# -0_1-0_8.net
KiCad netlist of a schematic drawn in EAGLE
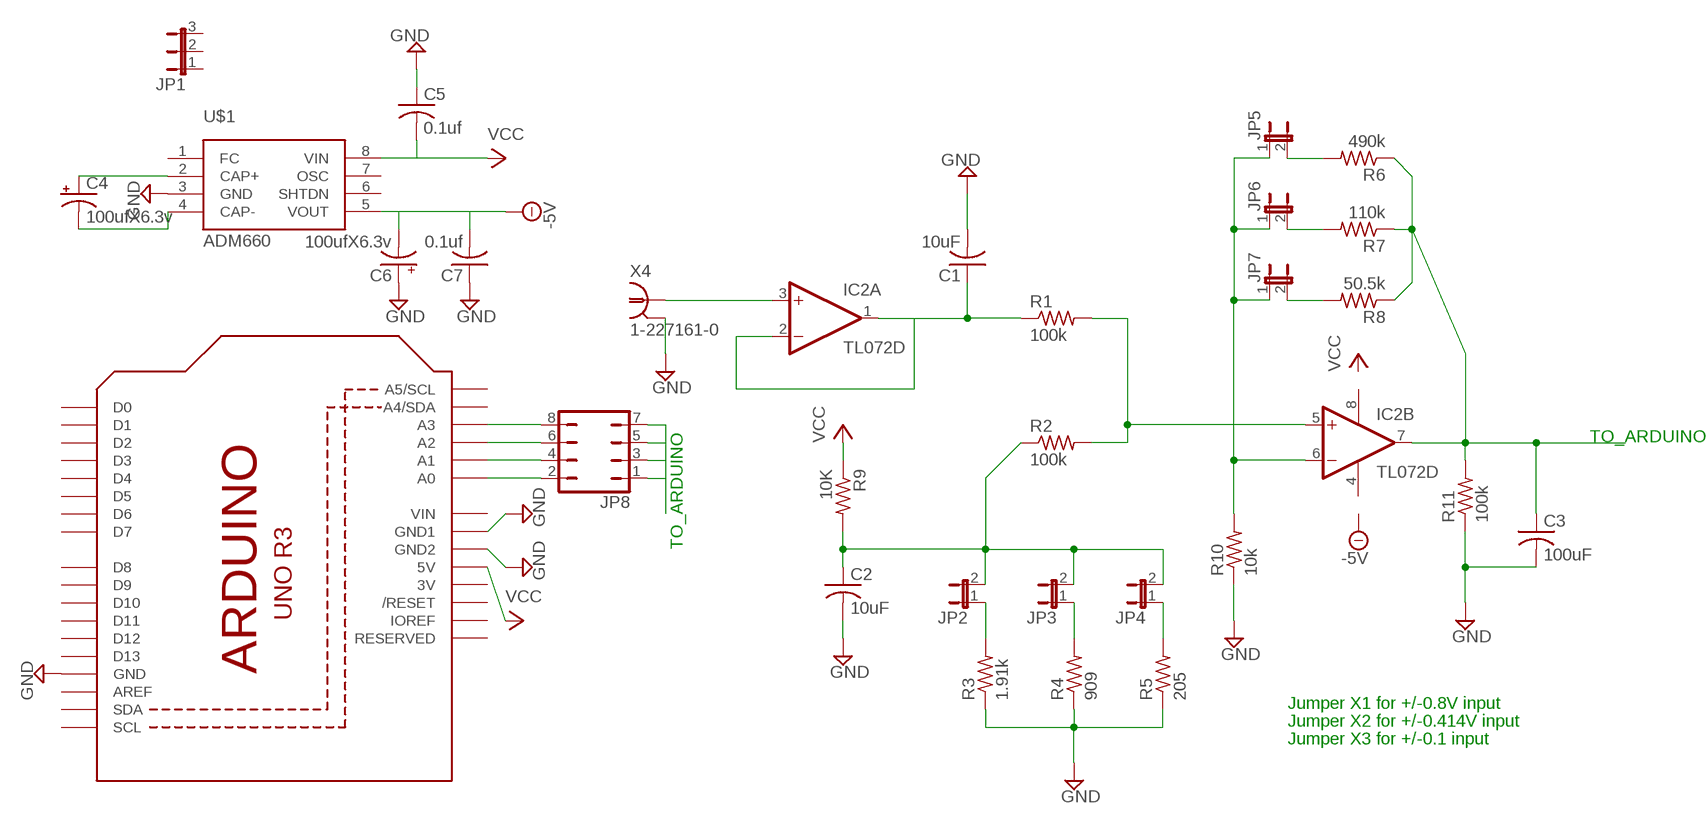
[diagram p0: schematic, sheet 1]

(export (version "E")
  (design (tool "Eeschema 10.0.6"))
  (components
    (comp (ref "C1")
      (value "10uF")
      (footprint "eagle-import:C0603")
      (libsource (lib "eagle-import") (part "resistor_C-USC0603"))
    )
    (comp (ref "C2")
      (value "10uF")
      (footprint "eagle-import:C0603")
      (libsource (lib "eagle-import") (part "resistor_C-USC0603"))
    )
    (comp (ref "C3")
      (value "100uF")
      (footprint "eagle-import:C0603")
      (libsource (lib "eagle-import") (part "resistor_C-USC0603"))
    )
    (comp (ref "C4")
      (value "100ufX6.3v")
      (footprint "eagle-import:153CLV-0605")
      (libsource (lib "eagle-import") (part "CPOL-US153CLV-0605"))
    )
    (comp (ref "C5")
      (value "0.1uf")
      (footprint "eagle-import:C0603")
      (libsource (lib "eagle-import") (part "C-USC0603"))
    )
    (comp (ref "C6")
      (value "100ufX6.3v")
      (footprint "eagle-import:153CLV-0605")
      (libsource (lib "eagle-import") (part "CPOL-US153CLV-0605"))
    )
    (comp (ref "C7")
      (value "0.1uf")
      (footprint "eagle-import:C0603")
      (libsource (lib "eagle-import") (part "C-USC0603"))
    )
    (comp (ref "IC2")
      (value "TL072D")
      (footprint "eagle-import:SO08")
      (libsource (lib "eagle-import") (part "TL072D"))
    )
    (comp (ref "JP1")
      (value "JP2E")
      (footprint "eagle-import:JP2")
      (libsource (lib "eagle-import") (part "JP2E"))
    )
    (comp (ref "JP2")
      (value "JP1E")
      (footprint "eagle-import:JP1")
      (libsource (lib "eagle-import") (part "JP1E"))
    )
    (comp (ref "JP3")
      (value "JP1E")
      (footprint "eagle-import:JP1")
      (libsource (lib "eagle-import") (part "JP1E"))
    )
    (comp (ref "JP4")
      (value "JP1E")
      (footprint "eagle-import:JP1")
      (libsource (lib "eagle-import") (part "JP1E"))
    )
    (comp (ref "JP5")
      (value "JP1E")
      (footprint "eagle-import:JP1")
      (libsource (lib "eagle-import") (part "JP1E"))
    )
    (comp (ref "JP6")
      (value "JP1E")
      (footprint "eagle-import:JP1")
      (libsource (lib "eagle-import") (part "JP1E"))
    )
    (comp (ref "JP7")
      (value "JP1E")
      (footprint "eagle-import:JP1")
      (libsource (lib "eagle-import") (part "JP1E"))
    )
    (comp (ref "JP8")
      (value "JP4Q")
      (footprint "eagle-import:JP4Q")
      (libsource (lib "eagle-import") (part "JP4Q"))
    )
    (comp (ref "R1")
      (value "100k")
      (footprint "eagle-import:R0603")
      (libsource (lib "eagle-import") (part "R-US_R0603"))
    )
    (comp (ref "R2")
      (value "100k")
      (footprint "eagle-import:R0603")
      (libsource (lib "eagle-import") (part "R-US_R0603"))
    )
    (comp (ref "R3")
      (value "1.91k")
      (footprint "eagle-import:R0603")
      (libsource (lib "eagle-import") (part "R-US_R0603"))
    )
    (comp (ref "R4")
      (value "909")
      (footprint "eagle-import:R0603")
      (libsource (lib "eagle-import") (part "R-US_R0603"))
    )
    (comp (ref "R5")
      (value "205")
      (footprint "eagle-import:R0603")
      (libsource (lib "eagle-import") (part "R-US_R0603"))
    )
    (comp (ref "R6")
      (value "490k")
      (footprint "eagle-import:R0603")
      (libsource (lib "eagle-import") (part "R-US_R0603"))
    )
    (comp (ref "R7")
      (value "110k")
      (footprint "eagle-import:R0603")
      (libsource (lib "eagle-import") (part "R-US_R0603"))
    )
    (comp (ref "R8")
      (value "50.5k")
      (footprint "eagle-import:R0603")
      (libsource (lib "eagle-import") (part "R-US_R0603"))
    )
    (comp (ref "R9")
      (value "10K")
      (footprint "eagle-import:R0603")
      (libsource (lib "eagle-import") (part "R-US_R0603"))
    )
    (comp (ref "R10")
      (value "10k")
      (footprint "eagle-import:R0603")
      (libsource (lib "eagle-import") (part "R-US_R0603"))
    )
    (comp (ref "R11")
      (value "100k")
      (footprint "eagle-import:R0603")
      (libsource (lib "eagle-import") (part "R-US_R0603"))
    )
    (comp (ref "U$1")
      (value "ADM660")
      (footprint "eagle-import:SO8")
      (libsource (lib "eagle-import") (part "TC1121COA"))
    )
    (comp (ref "U1")
      (value "ARDUINOR3-DIMENSION")
      (footprint "eagle-import:ARDUINOR3")
      (libsource (lib "eagle-import") (part "ARDUINOR3-DIMENSION"))
    )
    (comp (ref "X4")
      (value "1-227161-0")
      (footprint "eagle-import:AMP_227161")
      (fields (field (name "MF") "TYCO ELECTRONICS") (field (name "MPN") "1-227161"))
      (libsource (lib "eagle-import") (part "?2271611--0"))
    )
  )
  (nets
    (net (code "1") (name "-5V") (class "Default")
      (node (ref "C6") (pin "-") (pinfunction "-_-") (pintype "passive"))
      (node (ref "C7") (pin "2") (pinfunction "2_2") (pintype "passive"))
      (node (ref "U$1") (pin "5") (pinfunction "VOUT_5") (pintype "bidirectional"))
    )
    (net (code "2") (name "/3V") (class "Default")
      (node (ref "U1") (pin "3V") (pinfunction "3V_3V") (pintype "power_in"))
    )
    (net (code "3") (name "/TO_ARDUINO") (class "Default")
      (node (ref "C3") (pin "1") (pinfunction "1_1") (pintype "passive"))
      (node (ref "IC2") (pin "7") (pinfunction "OUT_7") (pintype "output"))
      (node (ref "JP8") (pin "1") (pinfunction "1_1") (pintype "passive"))
      (node (ref "JP8") (pin "3") (pinfunction "3_3") (pintype "passive"))
      (node (ref "JP8") (pin "5") (pinfunction "5_5") (pintype "passive"))
      (node (ref "JP8") (pin "7") (pinfunction "7_7") (pintype "passive"))
      (node (ref "R11") (pin "2") (pinfunction "2_2") (pintype "passive"))
      (node (ref "R6") (pin "1") (pinfunction "1_1") (pintype "passive"))
      (node (ref "R7") (pin "1") (pinfunction "1_1") (pintype "passive"))
      (node (ref "R8") (pin "1") (pinfunction "1_1") (pintype "passive"))
    )
    (net (code "4") (name "/V+") (class "Default")
      (node (ref "IC2") (pin "8") (pinfunction "V+_8") (pintype "power_in"))
    )
    (net (code "5") (name "/V-") (class "Default")
      (node (ref "IC2") (pin "4") (pinfunction "V-_4") (pintype "power_in"))
    )
    (net (code "6") (name "/VIN") (class "Default")
      (node (ref "U1") (pin "VIN") (pinfunction "VIN_VIN") (pintype "power_in"))
    )
    (net (code "7") (name "GND") (class "Default")
      (node (ref "C1") (pin "2") (pinfunction "2_2") (pintype "passive"))
      (node (ref "C2") (pin "2") (pinfunction "2_2") (pintype "passive"))
      (node (ref "C3") (pin "2") (pinfunction "2_2") (pintype "passive"))
      (node (ref "C5") (pin "1") (pinfunction "1_1") (pintype "passive"))
      (node (ref "C6") (pin "+") (pinfunction "+_+") (pintype "passive"))
      (node (ref "C7") (pin "1") (pinfunction "1_1") (pintype "passive"))
      (node (ref "R10") (pin "1") (pinfunction "1_1") (pintype "passive"))
      (node (ref "R11") (pin "1") (pinfunction "1_1") (pintype "passive"))
      (node (ref "R3") (pin "1") (pinfunction "1_1") (pintype "passive"))
      (node (ref "R4") (pin "1") (pinfunction "1_1") (pintype "passive"))
      (node (ref "R5") (pin "1") (pinfunction "1_1") (pintype "passive"))
      (node (ref "U$1") (pin "3") (pinfunction "GND_3") (pintype "bidirectional"))
      (node (ref "U1") (pin "GND") (pinfunction "GND_GND") (pintype "power_in"))
      (node (ref "U1") (pin "GND1") (pinfunction "GND1_GND1") (pintype "power_in"))
      (node (ref "U1") (pin "GND2") (pinfunction "GND2_GND2") (pintype "power_in"))
      (node (ref "X4") (pin "2") (pinfunction "GND_2") (pintype "power_in"))
    )
    (net (code "8") (name "Net-(C2-Pad1)") (class "Default")
      (node (ref "C2") (pin "1") (pinfunction "1_1") (pintype "passive"))
      (node (ref "JP2") (pin "2") (pinfunction "2_2") (pintype "passive"))
      (node (ref "JP3") (pin "2") (pinfunction "2_2") (pintype "passive"))
      (node (ref "JP4") (pin "2") (pinfunction "2_2") (pintype "passive"))
      (node (ref "R2") (pin "1") (pinfunction "1_1") (pintype "passive"))
      (node (ref "R9") (pin "2") (pinfunction "2_2") (pintype "passive"))
    )
    (net (code "9") (name "Net-(IC2A-+IN)") (class "Default")
      (node (ref "IC2") (pin "3") (pinfunction "+IN_3") (pintype "input"))
      (node (ref "X4") (pin "1") (pinfunction "1_1") (pintype "passive"))
    )
    (net (code "10") (name "Net-(IC2A--IN)") (class "Default")
      (node (ref "C1") (pin "1") (pinfunction "1_1") (pintype "passive"))
      (node (ref "IC2") (pin "1") (pinfunction "OUT_1") (pintype "output"))
      (node (ref "IC2") (pin "2") (pinfunction "-IN_2") (pintype "input"))
      (node (ref "R1") (pin "1") (pinfunction "1_1") (pintype "passive"))
    )
    (net (code "11") (name "Net-(IC2B-+IN)") (class "Default")
      (node (ref "IC2") (pin "5") (pinfunction "+IN_5") (pintype "input"))
      (node (ref "R1") (pin "2") (pinfunction "2_2") (pintype "passive"))
      (node (ref "R2") (pin "2") (pinfunction "2_2") (pintype "passive"))
    )
    (net (code "12") (name "Net-(IC2B--IN)") (class "Default")
      (node (ref "IC2") (pin "6") (pinfunction "-IN_6") (pintype "input"))
      (node (ref "JP5") (pin "1") (pinfunction "1_1") (pintype "passive"))
      (node (ref "JP6") (pin "1") (pinfunction "1_1") (pintype "passive"))
      (node (ref "JP7") (pin "1") (pinfunction "1_1") (pintype "passive"))
      (node (ref "R10") (pin "2") (pinfunction "2_2") (pintype "passive"))
    )
    (net (code "13") (name "Net-(JP2-Pad1)") (class "Default")
      (node (ref "JP2") (pin "1") (pinfunction "1_1") (pintype "passive"))
      (node (ref "R3") (pin "2") (pinfunction "2_2") (pintype "passive"))
    )
    (net (code "14") (name "Net-(JP3-Pad1)") (class "Default")
      (node (ref "JP3") (pin "1") (pinfunction "1_1") (pintype "passive"))
      (node (ref "R4") (pin "2") (pinfunction "2_2") (pintype "passive"))
    )
    (net (code "15") (name "Net-(JP4-Pad1)") (class "Default")
      (node (ref "JP4") (pin "1") (pinfunction "1_1") (pintype "passive"))
      (node (ref "R5") (pin "2") (pinfunction "2_2") (pintype "passive"))
    )
    (net (code "16") (name "Net-(JP5-Pad2)") (class "Default")
      (node (ref "JP5") (pin "2") (pinfunction "2_2") (pintype "passive"))
      (node (ref "R6") (pin "2") (pinfunction "2_2") (pintype "passive"))
    )
    (net (code "17") (name "Net-(JP6-Pad2)") (class "Default")
      (node (ref "JP6") (pin "2") (pinfunction "2_2") (pintype "passive"))
      (node (ref "R7") (pin "2") (pinfunction "2_2") (pintype "passive"))
    )
    (net (code "18") (name "Net-(JP7-Pad2)") (class "Default")
      (node (ref "JP7") (pin "2") (pinfunction "2_2") (pintype "passive"))
      (node (ref "R8") (pin "2") (pinfunction "2_2") (pintype "passive"))
    )
    (net (code "19") (name "Net-(JP8-Pad2)") (class "Default")
      (node (ref "JP8") (pin "2") (pinfunction "2_2") (pintype "passive"))
      (node (ref "U1") (pin "A0") (pinfunction "A0_A0") (pintype "bidirectional"))
    )
    (net (code "20") (name "Net-(JP8-Pad4)") (class "Default")
      (node (ref "JP8") (pin "4") (pinfunction "4_4") (pintype "passive"))
      (node (ref "U1") (pin "A1") (pinfunction "A1_A1") (pintype "bidirectional"))
    )
    (net (code "21") (name "Net-(JP8-Pad6)") (class "Default")
      (node (ref "JP8") (pin "6") (pinfunction "6_6") (pintype "passive"))
      (node (ref "U1") (pin "A2") (pinfunction "A2_A2") (pintype "bidirectional"))
    )
    (net (code "22") (name "Net-(JP8-Pad8)") (class "Default")
      (node (ref "JP8") (pin "8") (pinfunction "8_8") (pintype "passive"))
      (node (ref "U1") (pin "A3") (pinfunction "A3_A3") (pintype "bidirectional"))
    )
    (net (code "23") (name "Net-(U$1-CAP+)") (class "Default")
      (node (ref "C4") (pin "+") (pinfunction "+_+") (pintype "passive"))
      (node (ref "U$1") (pin "2") (pinfunction "CAP+_2") (pintype "bidirectional"))
    )
    (net (code "24") (name "Net-(U$1-CAP-)") (class "Default")
      (node (ref "C4") (pin "-") (pinfunction "-_-") (pintype "passive"))
      (node (ref "U$1") (pin "4") (pinfunction "CAP-_4") (pintype "bidirectional"))
    )
    (net (code "25") (name "VCC") (class "Default")
      (node (ref "C5") (pin "2") (pinfunction "2_2") (pintype "passive"))
      (node (ref "R9") (pin "1") (pinfunction "1_1") (pintype "passive"))
      (node (ref "U$1") (pin "8") (pinfunction "VIN_8") (pintype "bidirectional"))
      (node (ref "U1") (pin "5V") (pinfunction "5V_5V") (pintype "power_in"))
    )
    (net (code "26") (name "unconnected-(JP1-Pad1)") (class "Default")
      (node (ref "JP1") (pin "1") (pinfunction "1_1") (pintype "passive"))
    )
    (net (code "27") (name "unconnected-(JP1-Pad2)") (class "Default")
      (node (ref "JP1") (pin "2") (pinfunction "2_2") (pintype "passive"))
    )
    (net (code "28") (name "unconnected-(JP1-Pad3)") (class "Default")
      (node (ref "JP1") (pin "3") (pinfunction "3_3") (pintype "passive"))
    )
    (net (code "29") (name "unconnected-(U$1-FC-Pad1)") (class "Default")
      (node (ref "U$1") (pin "1") (pinfunction "FC_1") (pintype "bidirectional"))
    )
    (net (code "30") (name "unconnected-(U$1-OSC-Pad7)") (class "Default")
      (node (ref "U$1") (pin "7") (pinfunction "OSC_7") (pintype "bidirectional"))
    )
    (net (code "31") (name "unconnected-(U$1-SHTDN-Pad6)") (class "Default")
      (node (ref "U$1") (pin "6") (pinfunction "SHTDN_6") (pintype "bidirectional"))
    )
    (net (code "32") (name "unconnected-(U1-A4{slash}SDA-PadA4)") (class "Default")
      (node (ref "U1") (pin "A4") (pinfunction "A4/SDA_A4") (pintype "bidirectional"))
    )
    (net (code "33") (name "unconnected-(U1-A5{slash}SCL-PadA5)") (class "Default")
      (node (ref "U1") (pin "A5") (pinfunction "A5/SCL_A5") (pintype "bidirectional"))
    )
    (net (code "34") (name "unconnected-(U1-PadAREF)") (class "Default")
      (node (ref "U1") (pin "AREF") (pinfunction "AREF_AREF") (pintype "bidirectional"))
    )
    (net (code "35") (name "unconnected-(U1-PadD0)") (class "Default")
      (node (ref "U1") (pin "D0") (pinfunction "D0_D0") (pintype "bidirectional"))
    )
    (net (code "36") (name "unconnected-(U1-PadD1)") (class "Default")
      (node (ref "U1") (pin "D1") (pinfunction "D1_D1") (pintype "bidirectional"))
    )
    (net (code "37") (name "unconnected-(U1-PadD2)") (class "Default")
      (node (ref "U1") (pin "D2") (pinfunction "D2_D2") (pintype "bidirectional"))
    )
    (net (code "38") (name "unconnected-(U1-PadD3)") (class "Default")
      (node (ref "U1") (pin "D3") (pinfunction "D3_D3") (pintype "bidirectional"))
    )
    (net (code "39") (name "unconnected-(U1-PadD4)") (class "Default")
      (node (ref "U1") (pin "D4") (pinfunction "D4_D4") (pintype "bidirectional"))
    )
    (net (code "40") (name "unconnected-(U1-PadD5)") (class "Default")
      (node (ref "U1") (pin "D5") (pinfunction "D5_D5") (pintype "bidirectional"))
    )
    (net (code "41") (name "unconnected-(U1-PadD6)") (class "Default")
      (node (ref "U1") (pin "D6") (pinfunction "D6_D6") (pintype "bidirectional"))
    )
    (net (code "42") (name "unconnected-(U1-PadD7)") (class "Default")
      (node (ref "U1") (pin "D7") (pinfunction "D7_D7") (pintype "bidirectional"))
    )
    (net (code "43") (name "unconnected-(U1-PadD8)") (class "Default")
      (node (ref "U1") (pin "D8") (pinfunction "D8_D8") (pintype "bidirectional"))
    )
    (net (code "44") (name "unconnected-(U1-PadD9)") (class "Default")
      (node (ref "U1") (pin "D9") (pinfunction "D9_D9") (pintype "bidirectional"))
    )
    (net (code "45") (name "unconnected-(U1-PadD10)") (class "Default")
      (node (ref "U1") (pin "D10") (pinfunction "D10_D10") (pintype "bidirectional"))
    )
    (net (code "46") (name "unconnected-(U1-PadD11)") (class "Default")
      (node (ref "U1") (pin "D11") (pinfunction "D11_D11") (pintype "bidirectional"))
    )
    (net (code "47") (name "unconnected-(U1-PadD12)") (class "Default")
      (node (ref "U1") (pin "D12") (pinfunction "D12_D12") (pintype "bidirectional"))
    )
    (net (code "48") (name "unconnected-(U1-PadD13)") (class "Default")
      (node (ref "U1") (pin "D13") (pinfunction "D13_D13") (pintype "bidirectional"))
    )
    (net (code "49") (name "unconnected-(U1-PadIOREF)") (class "Default")
      (node (ref "U1") (pin "IOREF") (pinfunction "IOREF_IOREF") (pintype "output"))
    )
    (net (code "50") (name "unconnected-(U1-PadRESERVED)") (class "Default")
      (node (ref "U1") (pin "RESERVED") (pinfunction "RESERVED_RESERVED") (pintype "no_connect"))
    )
    (net (code "51") (name "unconnected-(U1-PadSCL)") (class "Default")
      (node (ref "U1") (pin "SCL") (pinfunction "SCL_SCL") (pintype "bidirectional"))
    )
    (net (code "52") (name "unconnected-(U1-PadSDA)") (class "Default")
      (node (ref "U1") (pin "SDA") (pinfunction "SDA_SDA") (pintype "bidirectional"))
    )
    (net (code "53") (name "unconnected-(U1-{slash}RESET-PadRESET)") (class "Default")
      (node (ref "U1") (pin "RESET") (pinfunction "/RESET_RESET") (pintype "bidirectional"))
    )
  )
)
